# STM32.net
KiCad netlist of a schematic drawn in Altium Designer
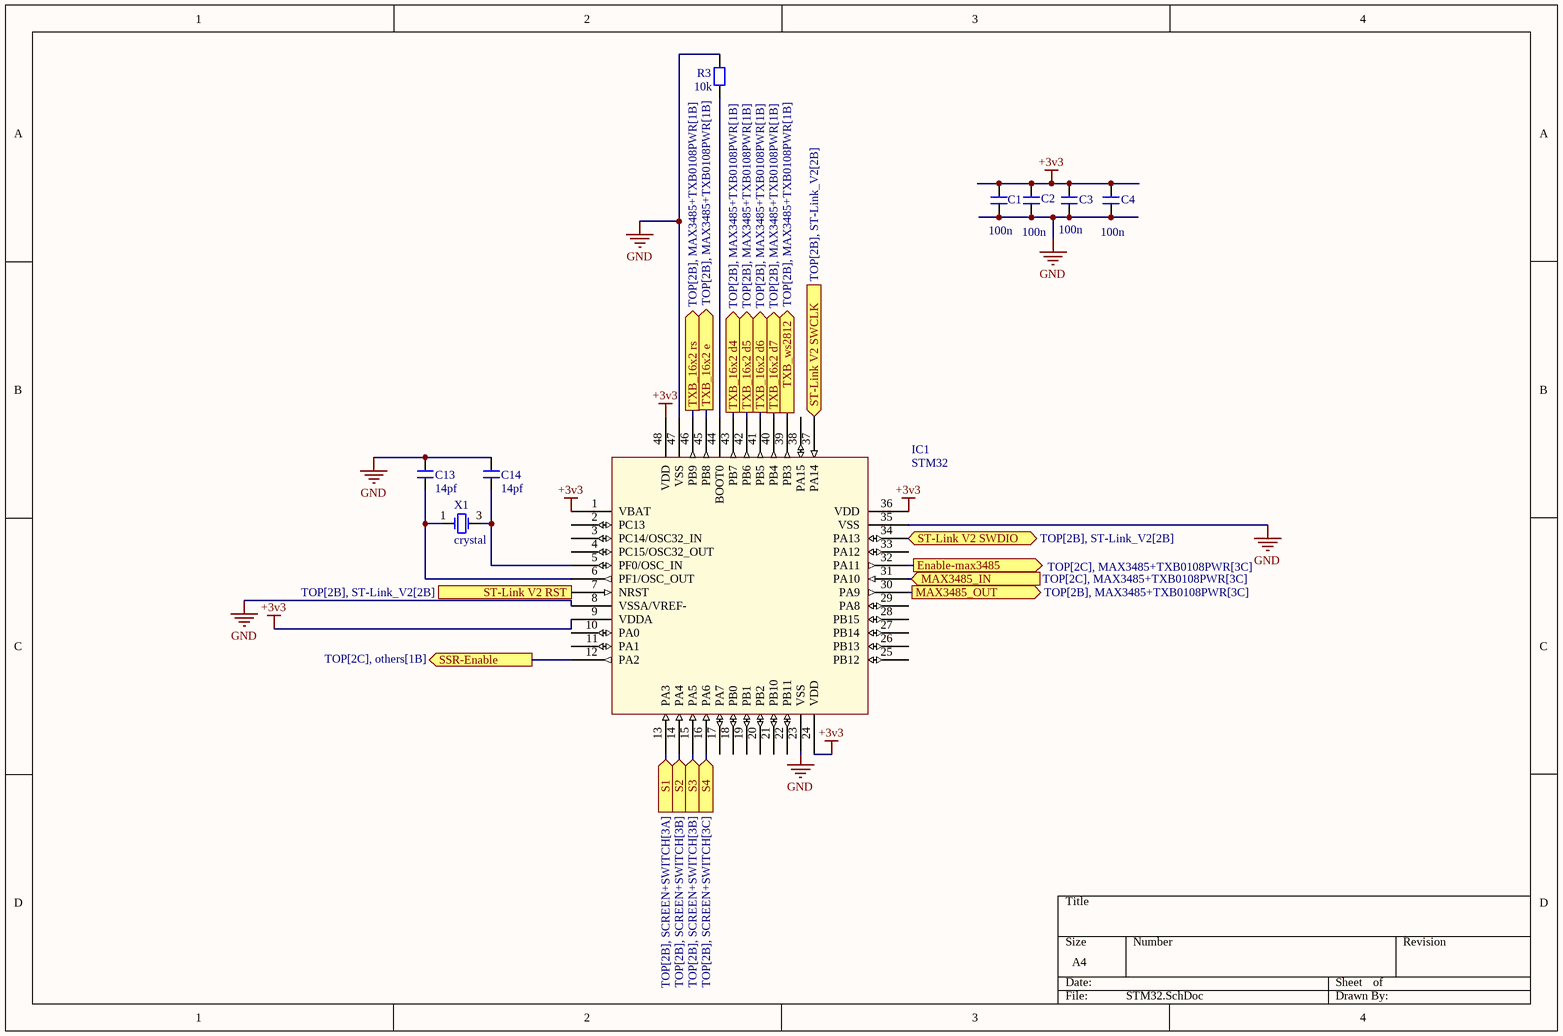
[diagram p0: STM32.SchDoc]

(export (version "E")
  (design (tool "Eeschema 10.0.6"))
  (components
    (comp (ref "C1") (value "100n") (footprint "0805") (libsource (lib "capacitor") (part "capacitor")))
    (comp (ref "C2") (value "100n") (footprint "0805") (libsource (lib "capacitor") (part "capacitor")))
    (comp (ref "C3") (value "100n") (footprint "0805") (libsource (lib "capacitor") (part "capacitor")))
    (comp (ref "C4") (value "100n") (footprint "0805") (libsource (lib "capacitor") (part "capacitor")))
    (comp (ref "C13") (value "14pf") (footprint "0805") (libsource (lib "capacitor") (part "capacitor")))
    (comp (ref "C14") (value "14pf") (footprint "0805") (libsource (lib "capacitor") (part "capacitor")))
    (comp (ref "IC1") (value "STM32") (footprint "STM32") (libsource (lib "STM32") (part "STM32")))
    (comp (ref "R3") (value "10k") (footprint "0805") (libsource (lib "resistor") (part "resistor")))
    (comp (ref "X1") (value "crystal") (footprint "crystal") (libsource (lib "crystal") (part "crystal")))
  )
  (nets
    (net (code "1") (name "+3v3") (class "Default")
      (node (ref "C1") (pin "1") (pinfunction "1_1") (pintype "passive"))
      (node (ref "C2") (pin "1") (pinfunction "1_1") (pintype "passive"))
      (node (ref "C3") (pin "1") (pinfunction "1_1") (pintype "passive"))
      (node (ref "C4") (pin "1") (pinfunction "1_1") (pintype "passive"))
      (node (ref "IC1") (pin "1") (pinfunction "VBAT_1") (pintype "power_in"))
      (node (ref "IC1") (pin "24") (pinfunction "VDD_24") (pintype "power_in"))
      (node (ref "IC1") (pin "36") (pinfunction "VDD_36") (pintype "power_in"))
      (node (ref "IC1") (pin "48") (pinfunction "VDD_48") (pintype "power_in"))
      (node (ref "IC1") (pin "9") (pinfunction "VDDA_9") (pintype "power_in"))
    )
    (net (code "2") (name "/Enable-max3485") (class "Default")
      (node (ref "IC1") (pin "32") (pinfunction "PA11_32") (pintype "output"))
    )
    (net (code "3") (name "/MAX3485_IN") (class "Default")
      (node (ref "IC1") (pin "31") (pinfunction "PA10_31") (pintype "input"))
    )
    (net (code "4") (name "/MAX3485_OUT") (class "Default")
      (node (ref "IC1") (pin "30") (pinfunction "PA9_30") (pintype "output"))
    )
    (net (code "5") (name "/S1") (class "Default")
      (node (ref "IC1") (pin "13") (pinfunction "PA3_13") (pintype "input"))
    )
    (net (code "6") (name "/S2") (class "Default")
      (node (ref "IC1") (pin "14") (pinfunction "PA4_14") (pintype "input"))
    )
    (net (code "7") (name "/S3") (class "Default")
      (node (ref "IC1") (pin "15") (pinfunction "PA5_15") (pintype "input"))
    )
    (net (code "8") (name "/S4") (class "Default")
      (node (ref "IC1") (pin "16") (pinfunction "PA6_16") (pintype "input"))
    )
    (net (code "9") (name "/SSR-Enable") (class "Default")
      (node (ref "IC1") (pin "12") (pinfunction "PA2_12") (pintype "output"))
    )
    (net (code "10") (name "/ST-Link V2 RST") (class "Default")
      (node (ref "IC1") (pin "7") (pinfunction "NRST_7") (pintype "input"))
    )
    (net (code "11") (name "/ST-Link V2 SWCLK") (class "Default")
      (node (ref "IC1") (pin "37") (pinfunction "PA14_37") (pintype "input"))
    )
    (net (code "12") (name "/ST-Link V2 SWDIO") (class "Default")
      (node (ref "IC1") (pin "34") (pinfunction "PA13_34") (pintype "bidirectional"))
    )
    (net (code "13") (name "/TXB_16x2 d4") (class "Default")
      (node (ref "IC1") (pin "43") (pinfunction "PB7_43") (pintype "output"))
    )
    (net (code "14") (name "/TXB_16x2 d5") (class "Default")
      (node (ref "IC1") (pin "42") (pinfunction "PB6_42") (pintype "output"))
    )
    (net (code "15") (name "/TXB_16x2 d6") (class "Default")
      (node (ref "IC1") (pin "41") (pinfunction "PB5_41") (pintype "output"))
    )
    (net (code "16") (name "/TXB_16x2 d7") (class "Default")
      (node (ref "IC1") (pin "40") (pinfunction "PB4_40") (pintype "output"))
    )
    (net (code "17") (name "/TXB_16x2 e") (class "Default")
      (node (ref "IC1") (pin "45") (pinfunction "PB8_45") (pintype "output"))
    )
    (net (code "18") (name "/TXB_16x2 rs") (class "Default")
      (node (ref "IC1") (pin "46") (pinfunction "PB9_46") (pintype "output"))
    )
    (net (code "19") (name "/TXB_ws2812") (class "Default")
      (node (ref "IC1") (pin "39") (pinfunction "PB3_39") (pintype "output"))
    )
    (net (code "20") (name "GND") (class "Default")
      (node (ref "C1") (pin "2") (pintype "passive"))
      (node (ref "C13") (pin "1") (pinfunction "1_1") (pintype "passive"))
      (node (ref "C14") (pin "1") (pinfunction "1_1") (pintype "passive"))
      (node (ref "C2") (pin "2") (pintype "passive"))
      (node (ref "C3") (pin "2") (pintype "passive"))
      (node (ref "C4") (pin "2") (pintype "passive"))
      (node (ref "IC1") (pin "23") (pinfunction "VSS_23") (pintype "power_in"))
      (node (ref "IC1") (pin "35") (pinfunction "VSS_35") (pintype "power_in"))
      (node (ref "IC1") (pin "47") (pinfunction "VSS_47") (pintype "power_in"))
      (node (ref "IC1") (pin "8") (pinfunction "VSSA/VREF-_8") (pintype "power_in"))
      (node (ref "R3") (pin "1") (pinfunction "1_1") (pintype "passive"))
    )
    (net (code "21") (name "Net-(IC1-BOOT0)") (class "Default")
      (node (ref "IC1") (pin "44") (pinfunction "BOOT0_44") (pintype "passive"))
      (node (ref "R3") (pin "2") (pinfunction "2_2") (pintype "passive"))
    )
    (net (code "22") (name "Net-(IC1-PF0{slash}OSC_IN)") (class "Default")
      (node (ref "C14") (pin "2") (pintype "passive"))
      (node (ref "IC1") (pin "5") (pinfunction "PF0/OSC_IN_5") (pintype "bidirectional"))
      (node (ref "X1") (pin "3") (pinfunction "OSC2_3") (pintype "passive"))
    )
    (net (code "23") (name "Net-(IC1-PF1{slash}OSC_OUT)") (class "Default")
      (node (ref "C13") (pin "2") (pintype "passive"))
      (node (ref "IC1") (pin "6") (pinfunction "PF1/OSC_OUT_6") (pintype "output"))
      (node (ref "X1") (pin "1") (pinfunction "OSC1_1") (pintype "passive"))
    )
    (net (code "24") (name "unconnected-(IC1-PA0-Pad10)") (class "Default")
      (node (ref "IC1") (pin "10") (pinfunction "PA0_10") (pintype "bidirectional"))
    )
    (net (code "25") (name "unconnected-(IC1-PA1-Pad11)") (class "Default")
      (node (ref "IC1") (pin "11") (pinfunction "PA1_11") (pintype "bidirectional"))
    )
    (net (code "26") (name "unconnected-(IC1-PA7-Pad17)") (class "Default")
      (node (ref "IC1") (pin "17") (pinfunction "PA7_17") (pintype "bidirectional"))
    )
    (net (code "27") (name "unconnected-(IC1-PA8-Pad29)") (class "Default")
      (node (ref "IC1") (pin "29") (pinfunction "PA8_29") (pintype "bidirectional"))
    )
    (net (code "28") (name "unconnected-(IC1-PA12-Pad33)") (class "Default")
      (node (ref "IC1") (pin "33") (pinfunction "PA12_33") (pintype "bidirectional"))
    )
    (net (code "29") (name "unconnected-(IC1-PA15-Pad38)") (class "Default")
      (node (ref "IC1") (pin "38") (pinfunction "PA15_38") (pintype "bidirectional"))
    )
    (net (code "30") (name "unconnected-(IC1-PB0-Pad18)") (class "Default")
      (node (ref "IC1") (pin "18") (pinfunction "PB0_18") (pintype "bidirectional"))
    )
    (net (code "31") (name "unconnected-(IC1-PB1-Pad19)") (class "Default")
      (node (ref "IC1") (pin "19") (pinfunction "PB1_19") (pintype "bidirectional"))
    )
    (net (code "32") (name "unconnected-(IC1-PB2-Pad20)") (class "Default")
      (node (ref "IC1") (pin "20") (pinfunction "PB2_20") (pintype "bidirectional"))
    )
    (net (code "33") (name "unconnected-(IC1-PB10-Pad21)") (class "Default")
      (node (ref "IC1") (pin "21") (pinfunction "PB10_21") (pintype "bidirectional"))
    )
    (net (code "34") (name "unconnected-(IC1-PB11-Pad22)") (class "Default")
      (node (ref "IC1") (pin "22") (pinfunction "PB11_22") (pintype "bidirectional"))
    )
    (net (code "35") (name "unconnected-(IC1-PB12-Pad25)") (class "Default")
      (node (ref "IC1") (pin "25") (pinfunction "PB12_25") (pintype "bidirectional"))
    )
    (net (code "36") (name "unconnected-(IC1-PB13-Pad26)") (class "Default")
      (node (ref "IC1") (pin "26") (pinfunction "PB13_26") (pintype "bidirectional"))
    )
    (net (code "37") (name "unconnected-(IC1-PB14-Pad27)") (class "Default")
      (node (ref "IC1") (pin "27") (pinfunction "PB14_27") (pintype "bidirectional"))
    )
    (net (code "38") (name "unconnected-(IC1-PB15-Pad28)") (class "Default")
      (node (ref "IC1") (pin "28") (pinfunction "PB15_28") (pintype "bidirectional"))
    )
    (net (code "39") (name "unconnected-(IC1-PC13-Pad2)") (class "Default")
      (node (ref "IC1") (pin "2") (pinfunction "PC13_2") (pintype "bidirectional"))
    )
    (net (code "40") (name "unconnected-(IC1-PC14{slash}OSC32_IN-Pad3)") (class "Default")
      (node (ref "IC1") (pin "3") (pinfunction "PC14/OSC32_IN_3") (pintype "bidirectional"))
    )
    (net (code "41") (name "unconnected-(IC1-PC15{slash}OSC32_OUT-Pad4)") (class "Default")
      (node (ref "IC1") (pin "4") (pinfunction "PC15/OSC32_OUT_4") (pintype "bidirectional"))
    )
  )
)
